# Sauce_Dispenser.net
KiCad netlist of a schematic drawn in EasyEDA Pro
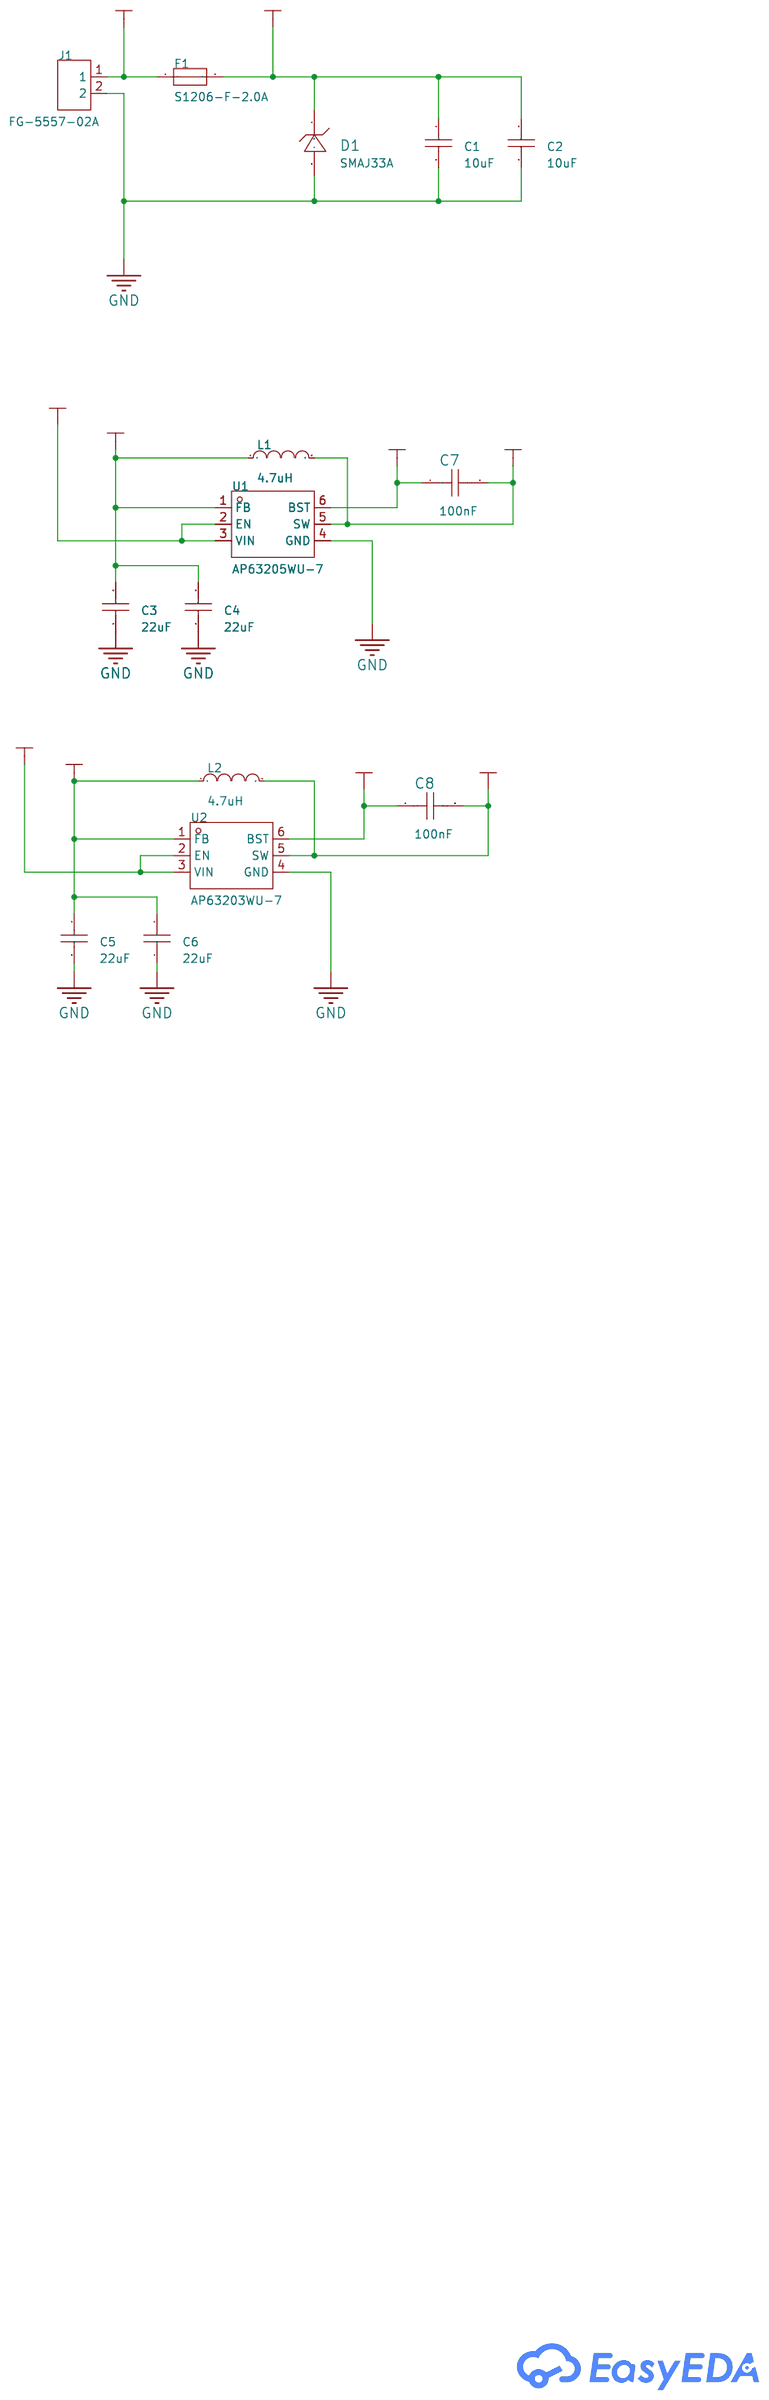
[diagram p0: P1]
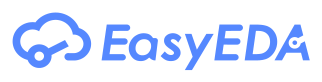
[diagram p1: P2]

(export (version "E")
  (design (tool "Eeschema 10.0.6"))
  (components
    (comp (ref "C1")
      (value "10uF")
      (footprint "easyedapro:C1206")
      (description "Capacitance:10uF Tolerance:±10% Tolerance:±10% Voltage Rating:50V Temperature Coefficient:X5R")
      (fields
        (field (name "Manufacturer Part") "CL31A106KBHNNNE")
        (field (name "Manufacturer") "SAMSUNG(三星)")
      )
      (libsource (lib "easyedapro") (part "CL31A106KBHNNNE"))
    )
    (comp (ref "C2")
      (value "10uF")
      (footprint "easyedapro:C1206")
      (description "Capacitance:10uF Tolerance:±10% Tolerance:±10% Voltage Rating:50V Temperature Coefficient:X5R")
      (fields
        (field (name "Manufacturer Part") "CL31A106KBHNNNE")
        (field (name "Manufacturer") "SAMSUNG(三星)")
      )
      (libsource (lib "easyedapro") (part "CL31A106KBHNNNE"))
    )
    (comp (ref "C3")
      (value "22uF")
      (footprint "easyedapro:C1206")
      (description "Capacitance:22uF Tolerance:±10% Tolerance:±10% Voltage Rating:25V Temperature Coefficient:X5R")
      (fields
        (field (name "Manufacturer Part") "CL31A226KAHNNNE")
        (field (name "Manufacturer") "SAMSUNG(三星)")
      )
      (libsource (lib "easyedapro") (part "CL31A226KAHNNNE"))
    )
    (comp (ref "C4")
      (value "22uF")
      (footprint "easyedapro:C1206")
      (description "Capacitance:22uF Tolerance:±10% Tolerance:±10% Voltage Rating:25V Temperature Coefficient:X5R")
      (fields
        (field (name "Manufacturer Part") "CL31A226KAHNNNE")
        (field (name "Manufacturer") "SAMSUNG(三星)")
      )
      (libsource (lib "easyedapro") (part "CL31A226KAHNNNE"))
    )
    (comp (ref "C5")
      (value "22uF")
      (footprint "easyedapro:C1206")
      (description "Capacitance:22uF Tolerance:±10% Tolerance:±10% Voltage Rating:25V Temperature Coefficient:X5R")
      (fields
        (field (name "Manufacturer Part") "CL31A226KAHNNNE")
        (field (name "Manufacturer") "SAMSUNG(三星)")
      )
      (libsource (lib "easyedapro") (part "CL31A226KAHNNNE"))
    )
    (comp (ref "C6")
      (value "22uF")
      (footprint "easyedapro:C1206")
      (description "Capacitance:22uF Tolerance:±10% Tolerance:±10% Voltage Rating:25V Temperature Coefficient:X5R")
      (fields
        (field (name "Manufacturer Part") "CL31A226KAHNNNE")
        (field (name "Manufacturer") "SAMSUNG(三星)")
      )
      (libsource (lib "easyedapro") (part "CL31A226KAHNNNE"))
    )
    (comp (ref "C7")
      (value "100nF")
      (footprint "easyedapro:C0603")
      (description "Capacitance:100nF Tolerance:±10% Tolerance:±10% Voltage Rating:50V Temperature Coefficient:X7R")
      (fields
        (field (name "Manufacturer Part") "CL10B104KB8NNNC")
        (field (name "Manufacturer") "SAMSUNG(三星)")
      )
      (libsource (lib "easyedapro") (part "CL10B104KB8NNNC"))
    )
    (comp (ref "C8")
      (value "100nF")
      (footprint "easyedapro:C0603")
      (description "Capacitance:100nF Tolerance:±10% Tolerance:±10% Voltage Rating:50V Temperature Coefficient:X7R")
      (fields
        (field (name "Manufacturer Part") "CL10B104KB8NNNC")
        (field (name "Manufacturer") "SAMSUNG(三星)")
      )
      (libsource (lib "easyedapro") (part "CL10B104KB8NNNC"))
    )
    (comp (ref "D1")
      (value "SMAJ33A")
      (footprint "easyedapro:SMA_L4.3-W2.6-LS5.2-RD")
      (fields (field (name "Manufacturer") "MDD"))
      (libsource (lib "easyedapro") (part "SMAJ33A_C113966"))
    )
    (comp (ref "F1")
      (value "S1206-F-2.0A")
      (footprint "easyedapro:F1206")
      (fields (field (name "Manufacturer") "SART(萨特)"))
      (libsource (lib "easyedapro") (part "S1206-F-2.0A"))
    )
    (comp (ref "J1")
      (value "FG-5557-02A")
      (footprint "easyedapro:CONN-TH_FG-5557-02A")
      (fields (field (name "Manufacturer") "FG(富港)"))
      (libsource (lib "easyedapro") (part "FG-5557-02A"))
    )
    (comp (ref "L1")
      (value "4.7uH")
      (footprint "easyedapro:IND-SMD_L5.4-W5.2")
      (fields
        (field (name "Manufacturer Part") "MWSA0503S-4R7MT")
        (field (name "Manufacturer") "Sunlord(顺络)")
      )
      (libsource (lib "easyedapro") (part "MWSA0503S-4R7MT"))
    )
    (comp (ref "L2")
      (value "4.7uH")
      (footprint "easyedapro:IND-SMD_L5.4-W5.2")
      (fields
        (field (name "Manufacturer Part") "MWSA0503S-4R7MT")
        (field (name "Manufacturer") "Sunlord(顺络)")
      )
      (libsource (lib "easyedapro") (part "MWSA0503S-4R7MT"))
    )
    (comp (ref "U1")
      (value "AP63205WU-7")
      (footprint "easyedapro:TSOT-23-6_L2.9-W1.6-P0.95-LS2.8-BL")
      (fields (field (name "Manufacturer") "DIODES(美台)"))
      (libsource (lib "easyedapro") (part "AP63205WU-7"))
    )
    (comp (ref "U2")
      (value "AP63203WU-7")
      (footprint "easyedapro:TSOT-26_L2.9-W1.6-P0.95-LS2.8-BL")
      (fields (field (name "Manufacturer") "DIODES(美台)"))
      (libsource (lib "easyedapro") (part "AP63203WU-7"))
    )
  )
  (nets
    (net (code "1") (name "BUCK3V3_BST") (class "Default")
      (node (ref "C8") (pin "1") (pinfunction "1_1") (pintype "input"))
      (node (ref "U2") (pin "6") (pinfunction "BST_6") (pintype "unspecified"))
    )
    (net (code "2") (name "BUCK3V3_SW") (class "Default")
      (node (ref "C8") (pin "2") (pinfunction "2_2") (pintype "input"))
      (node (ref "L2") (pin "2") (pinfunction "2_2") (pintype "unspecified"))
      (node (ref "U2") (pin "5") (pinfunction "SW_5") (pintype "unspecified"))
    )
    (net (code "3") (name "BUCK5_BST") (class "Default")
      (node (ref "C7") (pin "1") (pinfunction "1_1") (pintype "input"))
      (node (ref "U1") (pin "6") (pinfunction "BST_6") (pintype "unspecified"))
    )
    (net (code "4") (name "BUCK5_SW") (class "Default")
      (node (ref "C7") (pin "2") (pinfunction "2_2") (pintype "input"))
      (node (ref "L1") (pin "2") (pinfunction "2_2") (pintype "unspecified"))
      (node (ref "U1") (pin "5") (pinfunction "SW_5") (pintype "unspecified"))
    )
    (net (code "5") (name "GND") (class "Default")
      (node (ref "C1") (pin "2") (pinfunction "2_2") (pintype "input"))
      (node (ref "C2") (pin "1") (pinfunction "1_1") (pintype "input"))
      (node (ref "C3") (pin "1") (pinfunction "1_1") (pintype "input"))
      (node (ref "C4") (pin "1") (pinfunction "1_1") (pintype "input"))
      (node (ref "C5") (pin "1") (pinfunction "1_1") (pintype "input"))
      (node (ref "C6") (pin "1") (pinfunction "1_1") (pintype "input"))
      (node (ref "D1") (pin "2") (pinfunction "A_2") (pintype "input"))
      (node (ref "J1") (pin "2") (pinfunction "2_2") (pintype "unspecified"))
      (node (ref "U1") (pin "4") (pinfunction "GND_4") (pintype "unspecified"))
      (node (ref "U2") (pin "4") (pinfunction "GND_4") (pintype "unspecified"))
    )
    (net (code "6") (name "VCTRL_5V") (class "Default")
      (node (ref "C3") (pin "2") (pinfunction "2_2") (pintype "input"))
      (node (ref "C4") (pin "2") (pinfunction "2_2") (pintype "input"))
      (node (ref "L1") (pin "1") (pinfunction "1_1") (pintype "unspecified"))
      (node (ref "U1") (pin "1") (pinfunction "FB_1") (pintype "unspecified"))
    )
    (net (code "7") (name "VDD_3V3") (class "Default")
      (node (ref "C5") (pin "2") (pinfunction "2_2") (pintype "input"))
      (node (ref "C6") (pin "2") (pinfunction "2_2") (pintype "input"))
      (node (ref "L2") (pin "1") (pinfunction "1_1") (pintype "unspecified"))
      (node (ref "U2") (pin "1") (pinfunction "FB_1") (pintype "unspecified"))
    )
    (net (code "8") (name "VIN_24V_IN") (class "Default")
      (node (ref "F1") (pin "1") (pinfunction "1_1") (pintype "unspecified"))
      (node (ref "J1") (pin "1") (pinfunction "1_1") (pintype "unspecified"))
    )
    (net (code "9") (name "VIN_24V_PROTECTED") (class "Default")
      (node (ref "C1") (pin "1") (pinfunction "1_1") (pintype "input"))
      (node (ref "C2") (pin "2") (pinfunction "2_2") (pintype "input"))
      (node (ref "D1") (pin "1") (pinfunction "C_1") (pintype "input"))
      (node (ref "F1") (pin "2") (pinfunction "2_2") (pintype "unspecified"))
      (node (ref "U1") (pin "2") (pinfunction "EN_2") (pintype "unspecified"))
      (node (ref "U1") (pin "3") (pinfunction "VIN_3") (pintype "unspecified"))
      (node (ref "U2") (pin "2") (pinfunction "EN_2") (pintype "unspecified"))
      (node (ref "U2") (pin "3") (pinfunction "VIN_3") (pintype "unspecified"))
    )
  )
)
